# NADP.net
KiCad netlist of a schematic drawn in Altium Designer
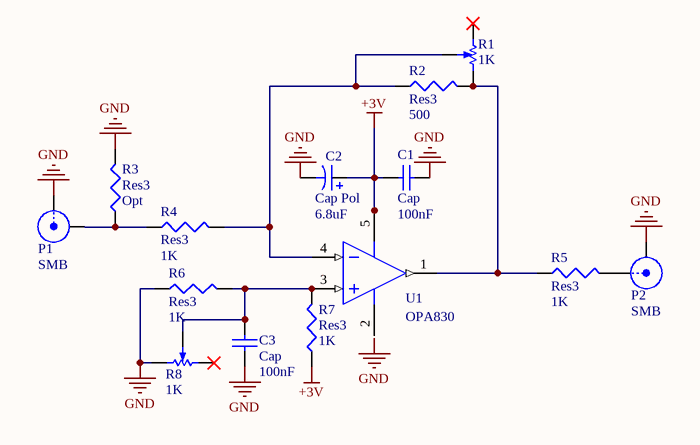
[diagram p0: NADP.SchDoc]

(export (version "E")
  (design (tool "Eeschema 10.0.6"))
  (components
    (comp (ref "C1")
      (value "Cap")
      (footprint "1608[0603]")
      (description "Capacitor (Semiconductor SIM Model)")
      (fields (field (name "ALTIUM_VALUE") "100nF") (field (name "PUBLISHER") "Altium Limited"))
      (libsource (lib "Miscellaneous Devices") (part "Cap Semi"))
    )
    (comp (ref "C2")
      (value "Cap Pol")
      (footprint "1608[0603]")
      (description "Polarized Capacitor (Surface Mount)")
      (fields (field (name "ALTIUM_VALUE") "6.8uF") (field (name "PUBLISHER") "Altium Limited"))
      (libsource (lib "Miscellaneous Devices") (part "Cap Pol3"))
    )
    (comp (ref "C3")
      (value "Cap")
      (footprint "1608[0603]")
      (description "Capacitor (Semiconductor SIM Model)")
      (fields (field (name "ALTIUM_VALUE") "100nF") (field (name "PUBLISHER") "Altium Limited"))
      (libsource (lib "Miscellaneous Devices") (part "Cap Semi"))
    )
    (comp (ref "P1")
      (value "SMB")
      (footprint "SMB_V-RJ45")
      (description "SMB Straight Connector")
      (fields (field (name "PUBLISHER") "Altium Limited"))
      (libsource (lib "Miscellaneous Connectors") (part "SMB"))
    )
    (comp (ref "P2")
      (value "SMB")
      (footprint "SMB_V-RJ45")
      (description "SMB Straight Connector")
      (fields (field (name "PUBLISHER") "Altium Limited"))
      (libsource (lib "Miscellaneous Connectors") (part "SMB"))
    )
    (comp (ref "R1")
      (value "1K")
      (footprint "POT4MM-2")
      (description "Square Trimming Potentiometer")
      (fields (field (name "PUBLISHER") "Altium Limited"))
      (libsource (lib "Miscellaneous Devices") (part "RPot SM"))
    )
    (comp (ref "R2")
      (value "Res3")
      (footprint "J1-0603")
      (description "Resistor")
      (fields (field (name "ALTIUM_VALUE") "500") (field (name "PUBLISHER") "Altium Limited"))
      (libsource (lib "Miscellaneous Devices") (part "Res3"))
    )
    (comp (ref "R3")
      (value "Res3")
      (footprint "J1-0603")
      (description "Resistor")
      (fields (field (name "ALTIUM_VALUE") "Opt") (field (name "PUBLISHER") "Altium Limited"))
      (libsource (lib "Miscellaneous Devices") (part "Res3"))
    )
    (comp (ref "R4")
      (value "Res3")
      (footprint "J1-0603")
      (description "Resistor")
      (fields (field (name "ALTIUM_VALUE") "1K") (field (name "PUBLISHER") "Altium Limited"))
      (libsource (lib "Miscellaneous Devices") (part "Res3"))
    )
    (comp (ref "R5")
      (value "Res3")
      (footprint "J1-0603")
      (description "Resistor")
      (fields (field (name "ALTIUM_VALUE") "1K") (field (name "PUBLISHER") "Altium Limited"))
      (libsource (lib "Miscellaneous Devices") (part "Res3"))
    )
    (comp (ref "R6")
      (value "Res3")
      (footprint "J1-0603")
      (description "Resistor")
      (fields (field (name "ALTIUM_VALUE") "1K") (field (name "PUBLISHER") "Altium Limited"))
      (libsource (lib "Miscellaneous Devices") (part "Res3"))
    )
    (comp (ref "R7")
      (value "Res3")
      (footprint "J1-0603")
      (description "Resistor")
      (fields (field (name "ALTIUM_VALUE") "1K") (field (name "PUBLISHER") "Altium Limited"))
      (libsource (lib "Miscellaneous Devices") (part "Res3"))
    )
    (comp (ref "R8")
      (value "1K")
      (footprint "POT4MM-2")
      (description "Square Trimming Potentiometer")
      (fields (field (name "PUBLISHER") "Altium Limited"))
      (libsource (lib "Miscellaneous Devices") (part "RPot SM"))
    )
    (comp (ref "U1")
      (value "OPA830")
      (footprint "SOT23-5_N")
      (description "300MHZ High-Speed Op Amp")
      (fields (field (name "PUBLISHER") "Altium Limited"))
      (libsource (lib "Maxim Operational Amplifier") (part "MAX477EUK-T"))
    )
  )
  (nets
    (net (code "1") (name "+3V") (class "Default")
      (node (ref "C1") (pin "1") (pinfunction "1_1") (pintype "passive"))
      (node (ref "C2") (pin "1") (pinfunction "1_1") (pintype "passive"))
      (node (ref "R7") (pin "1") (pinfunction "1_1") (pintype "passive"))
      (node (ref "U1") (pin "5") (pinfunction "VCC_5") (pintype "power_in"))
    )
    (net (code "2") (name "GND") (class "Default")
      (node (ref "C1") (pin "2") (pinfunction "2_2") (pintype "passive"))
      (node (ref "C2") (pin "2") (pinfunction "2_2") (pintype "passive"))
      (node (ref "C3") (pin "2") (pinfunction "2_2") (pintype "passive"))
      (node (ref "P1") (pin "1") (pinfunction "X_1") (pintype "passive"))
      (node (ref "P2") (pin "2") (pinfunction "Y_2") (pintype "passive"))
      (node (ref "R3") (pin "2") (pinfunction "2_2") (pintype "passive"))
      (node (ref "R6") (pin "1") (pinfunction "1_1") (pintype "passive"))
      (node (ref "R8") (pin "CW") (pinfunction "+_CW") (pintype "passive"))
    )
    (net (code "3") (name "Net-(P1-Y)") (class "Default")
      (node (ref "P1") (pin "2") (pinfunction "Y_2") (pintype "passive"))
      (node (ref "R3") (pin "1") (pinfunction "1_1") (pintype "passive"))
      (node (ref "R4") (pin "1") (pinfunction "1_1") (pintype "passive"))
    )
    (net (code "4") (name "Net-(P2-X)") (class "Default")
      (node (ref "P2") (pin "1") (pinfunction "X_1") (pintype "passive"))
      (node (ref "R5") (pin "2") (pinfunction "2_2") (pintype "passive"))
    )
    (net (code "5") (name "Net-(R1-+)") (class "Default")
      (node (ref "R1") (pin "CW") (pinfunction "+_CW") (pintype "passive"))
      (node (ref "R2") (pin "2") (pinfunction "2_2") (pintype "passive"))
      (node (ref "R5") (pin "1") (pinfunction "1_1") (pintype "passive"))
      (node (ref "U1") (pin "1") (pinfunction "OUT_1") (pintype "output"))
    )
    (net (code "6") (name "Net-(U1-IN+)") (class "Default")
      (node (ref "C3") (pin "1") (pinfunction "1_1") (pintype "passive"))
      (node (ref "R6") (pin "2") (pinfunction "2_2") (pintype "passive"))
      (node (ref "R7") (pin "2") (pinfunction "2_2") (pintype "passive"))
      (node (ref "R8") (pin "W") (pinfunction "W_W") (pintype "passive"))
      (node (ref "U1") (pin "3") (pinfunction "IN+_3") (pintype "input"))
    )
    (net (code "7") (name "Net-(U1-IN-)") (class "Default")
      (node (ref "R1") (pin "W") (pinfunction "W_W") (pintype "passive"))
      (node (ref "R2") (pin "1") (pinfunction "1_1") (pintype "passive"))
      (node (ref "R4") (pin "2") (pinfunction "2_2") (pintype "passive"))
      (node (ref "U1") (pin "4") (pinfunction "IN-_4") (pintype "input"))
    )
    (net (code "8") (name "unconnected-(R1---PadCCW)") (class "Default")
      (node (ref "R1") (pin "CCW") (pinfunction "-_CCW") (pintype "passive+no_connect"))
    )
    (net (code "9") (name "unconnected-(R8---PadCCW)") (class "Default")
      (node (ref "R8") (pin "CCW") (pinfunction "-_CCW") (pintype "passive+no_connect"))
    )
    (net (code "10") (name "unconnected-(U1-VEE-Pad2)") (class "Default")
      (node (ref "U1") (pin "2") (pinfunction "VEE_2") (pintype "power_in"))
    )
  )
)
